# SCH_camera_mount_detection_2024-06-10.net
KiCad netlist of a schematic drawn in EasyEDA
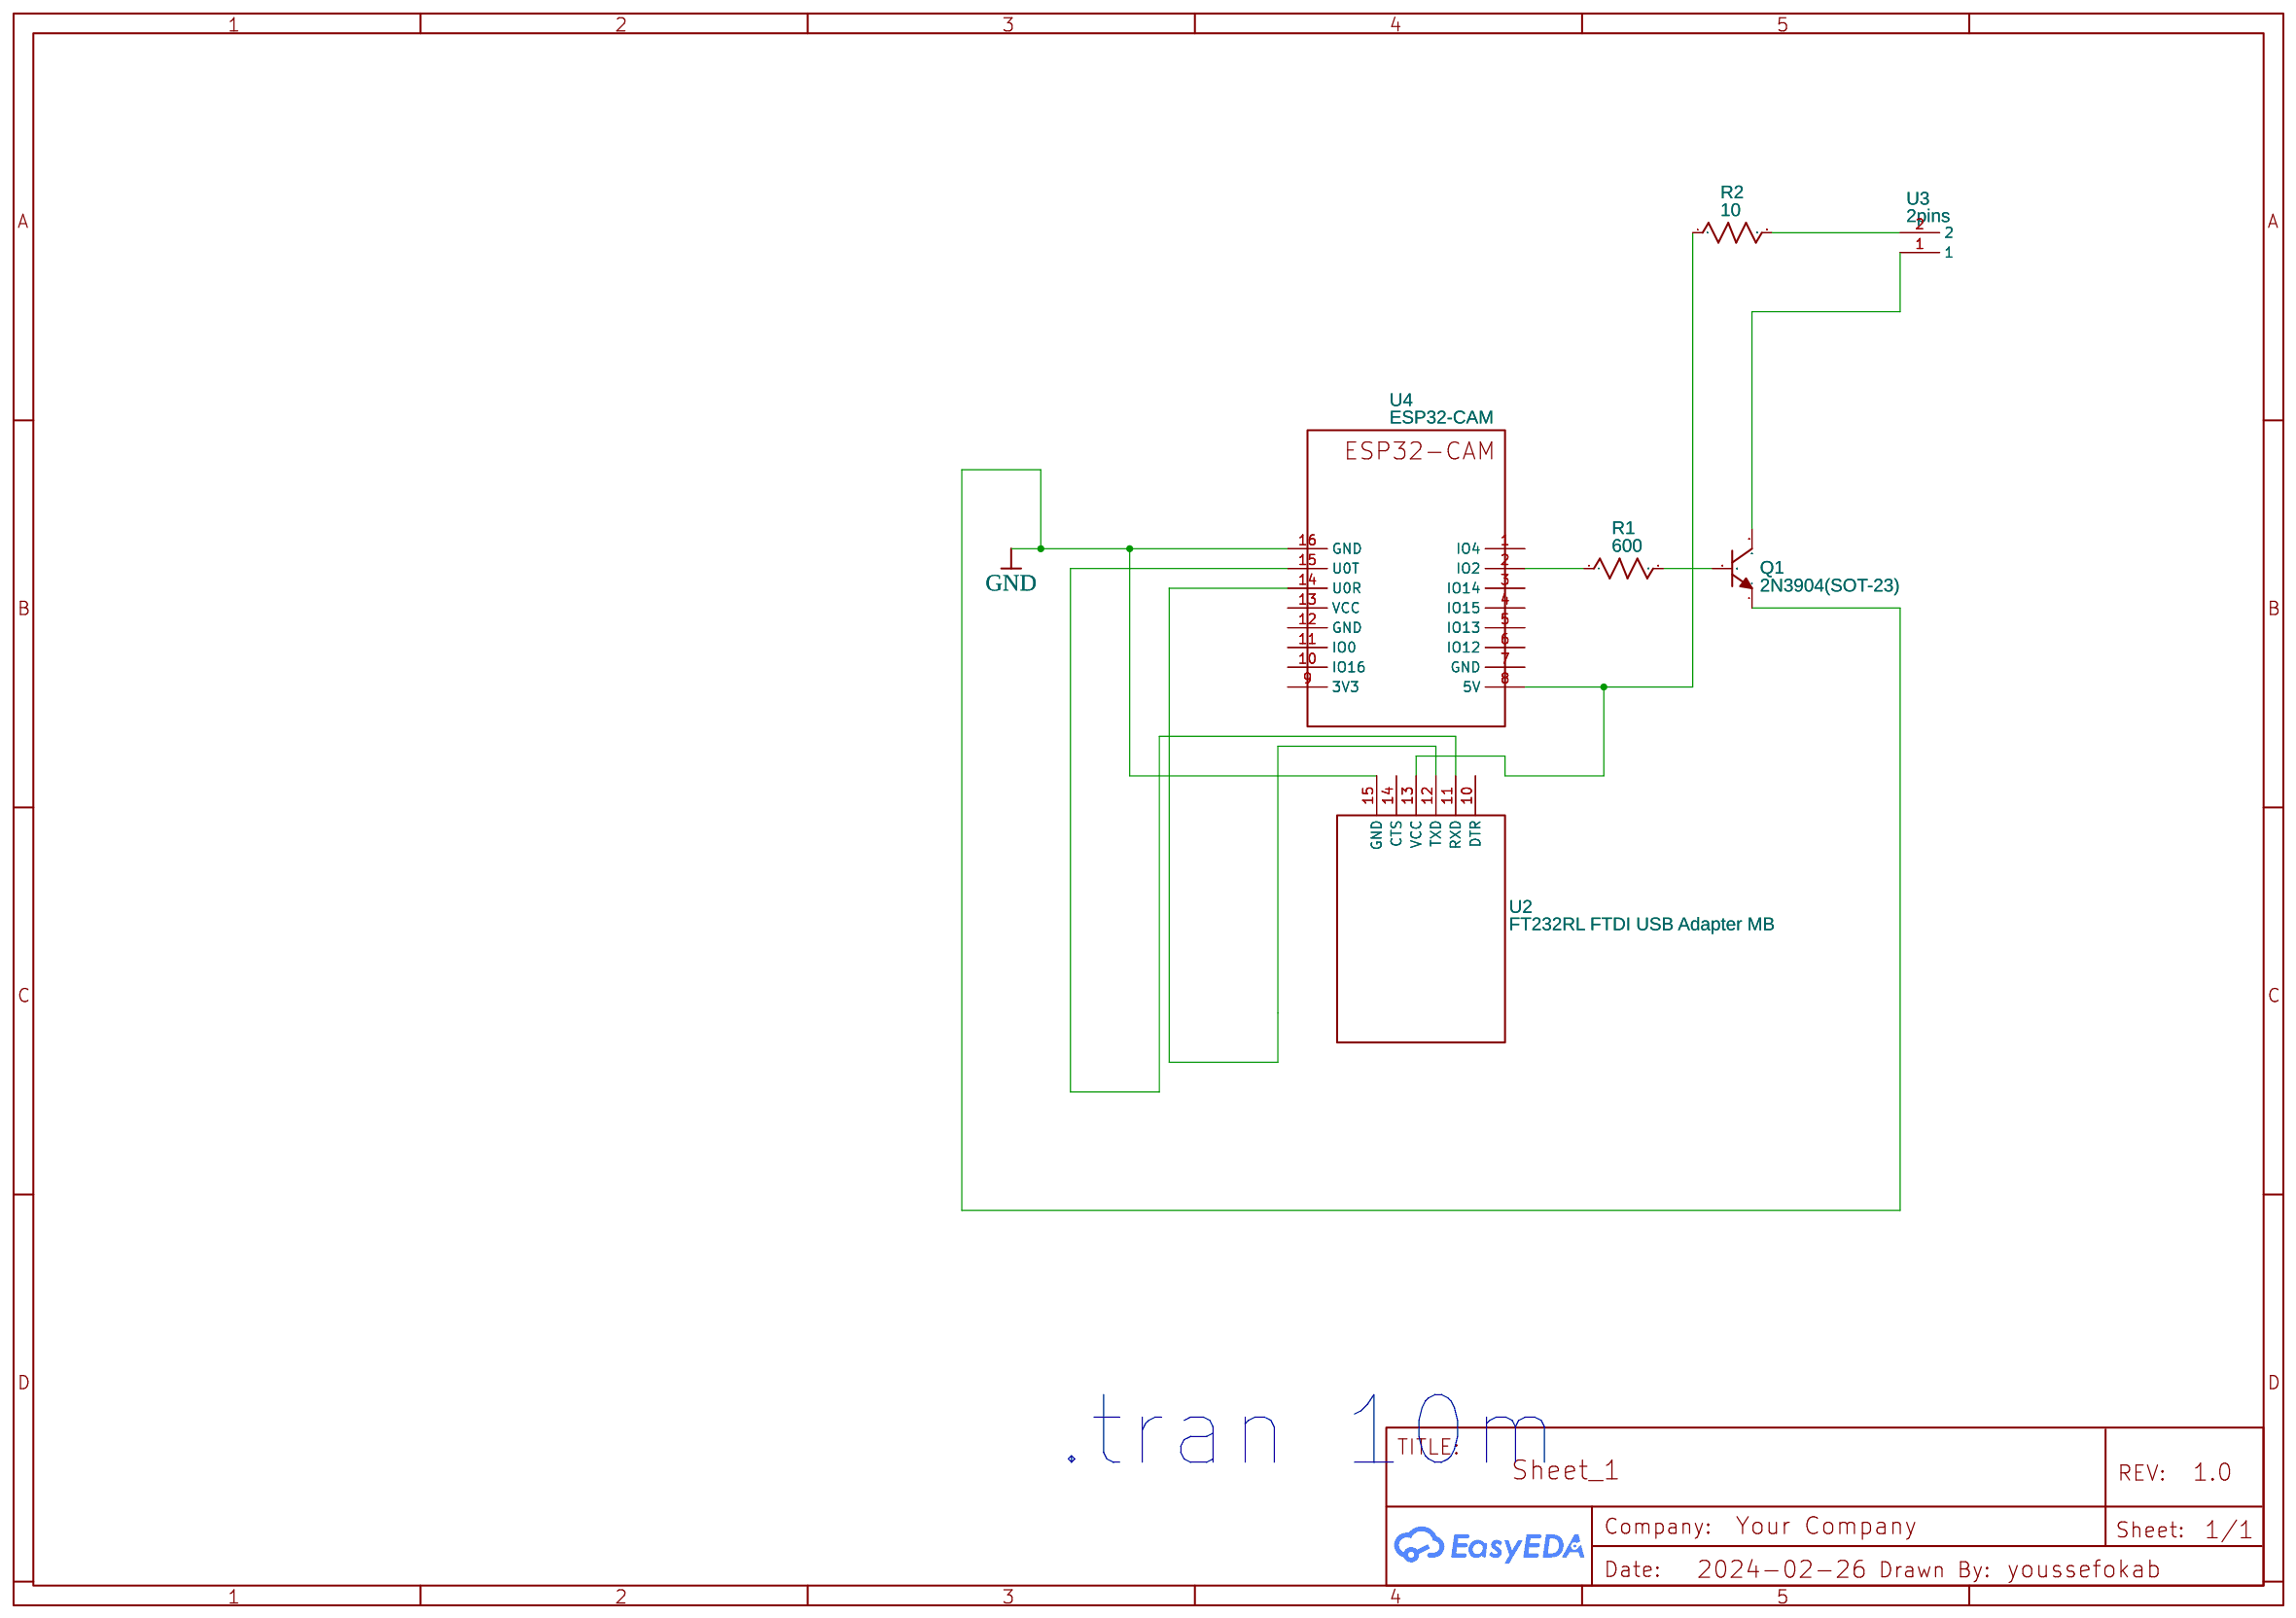
[diagram p0: schematic sheet]

(export (version "E")
  (design (tool "Eeschema 10.0.6"))
  (components
    (comp (ref "Q1")
      (value "2N3904(SOT-23)")
      (fields (field (name "Manufacturer Part") "2n3904S-RTK/PS") (field (name "Manufacturer") "KEC"))
      (libsource (lib "") (part "2N3904(SOT-23)"))
    )
    (comp (ref "R1") (value "600") (libsource (lib "") (part "R_0603_US")))
    (comp (ref "R2") (value "10") (libsource (lib "") (part "R_0603_US")))
    (comp (ref "U2")
      (value "FT232RL FTDI USB Adapter MB")
      (libsource (lib "") (part "FT232RL FTDI USB Adapter MB"))
    )
    (comp (ref "U3") (value "2pins") (libsource (lib "") (part "2pins")))
    (comp (ref "U4") (value "ESP32-CAM") (libsource (lib "") (part "ESP32-CAM")))
  )
  (nets
    (net (code "1") (name "GND") (class "Default")
      (node (ref "Q1") (pin "1") (pinfunction "E_1") (pintype "input"))
      (node (ref "U2") (pin "15") (pinfunction "GND_15") (pintype "unspecified"))
      (node (ref "U4") (pin "16") (pinfunction "GND_16") (pintype "unspecified"))
    )
    (net (code "2") (name "Net-(Q1-B)") (class "Default")
      (node (ref "Q1") (pin "2") (pinfunction "B_2") (pintype "input"))
      (node (ref "R1") (pin "2") (pinfunction "2_2") (pintype "unspecified"))
    )
    (net (code "3") (name "Net-(Q1-C)") (class "Default")
      (node (ref "Q1") (pin "3") (pinfunction "C_3") (pintype "input"))
      (node (ref "U3") (pin "1") (pinfunction "1_1") (pintype "unspecified"))
    )
    (net (code "4") (name "Net-(R2-Pad2)") (class "Default")
      (node (ref "R2") (pin "2") (pinfunction "2_2") (pintype "unspecified"))
      (node (ref "U3") (pin "2") (pinfunction "2_2") (pintype "unspecified"))
    )
    (net (code "5") (name "Net-(U2-RXD)") (class "Default")
      (node (ref "U2") (pin "11") (pinfunction "RXD_11") (pintype "unspecified"))
      (node (ref "U4") (pin "15") (pinfunction "U0T_15") (pintype "unspecified"))
    )
    (net (code "6") (name "Net-(U2-TXD)") (class "Default")
      (node (ref "U2") (pin "12") (pinfunction "TXD_12") (pintype "unspecified"))
      (node (ref "U4") (pin "14") (pinfunction "U0R_14") (pintype "unspecified"))
    )
    (net (code "7") (name "Net-(U2-VCC)") (class "Default")
      (node (ref "R2") (pin "1") (pinfunction "1_1") (pintype "unspecified"))
      (node (ref "U2") (pin "13") (pinfunction "VCC_13") (pintype "unspecified"))
      (node (ref "U4") (pin "8") (pinfunction "5V_8") (pintype "unspecified"))
    )
    (net (code "8") (name "Net-(U4-IO2)") (class "Default")
      (node (ref "R1") (pin "1") (pinfunction "1_1") (pintype "unspecified"))
      (node (ref "U4") (pin "2") (pinfunction "IO2_2") (pintype "unspecified"))
    )
    (net (code "9") (name "unconnected-(U2-CTS-Pad14)") (class "Default")
      (node (ref "U2") (pin "14") (pinfunction "CTS_14") (pintype "unspecified"))
    )
    (net (code "10") (name "unconnected-(U2-DTR-Pad10)") (class "Default")
      (node (ref "U2") (pin "10") (pinfunction "DTR_10") (pintype "unspecified"))
    )
    (net (code "11") (name "unconnected-(U4-3V3-Pad9)") (class "Default")
      (node (ref "U4") (pin "9") (pinfunction "3V3_9") (pintype "unspecified"))
    )
    (net (code "12") (name "unconnected-(U4-GND-Pad7)") (class "Default")
      (node (ref "U4") (pin "7") (pinfunction "GND_7") (pintype "unspecified"))
    )
    (net (code "13") (name "unconnected-(U4-GND-Pad12)") (class "Default")
      (node (ref "U4") (pin "12") (pinfunction "GND_12") (pintype "unspecified"))
    )
    (net (code "14") (name "unconnected-(U4-IO0-Pad11)") (class "Default")
      (node (ref "U4") (pin "11") (pinfunction "IO0_11") (pintype "unspecified"))
    )
    (net (code "15") (name "unconnected-(U4-IO4-Pad1)") (class "Default")
      (node (ref "U4") (pin "1") (pinfunction "IO4_1") (pintype "unspecified"))
    )
    (net (code "16") (name "unconnected-(U4-IO12-Pad6)") (class "Default")
      (node (ref "U4") (pin "6") (pinfunction "IO12_6") (pintype "unspecified"))
    )
    (net (code "17") (name "unconnected-(U4-IO13-Pad5)") (class "Default")
      (node (ref "U4") (pin "5") (pinfunction "IO13_5") (pintype "unspecified"))
    )
    (net (code "18") (name "unconnected-(U4-IO14-Pad3)") (class "Default")
      (node (ref "U4") (pin "3") (pinfunction "IO14_3") (pintype "unspecified"))
    )
    (net (code "19") (name "unconnected-(U4-IO15-Pad4)") (class "Default")
      (node (ref "U4") (pin "4") (pinfunction "IO15_4") (pintype "unspecified"))
    )
    (net (code "20") (name "unconnected-(U4-IO16-Pad10)") (class "Default")
      (node (ref "U4") (pin "10") (pinfunction "IO16_10") (pintype "unspecified"))
    )
    (net (code "21") (name "unconnected-(U4-VCC-Pad13)") (class "Default")
      (node (ref "U4") (pin "13") (pinfunction "VCC_13") (pintype "unspecified"))
    )
  )
)
